# capmodule.net
KiCad netlist of a schematic drawn in EAGLE
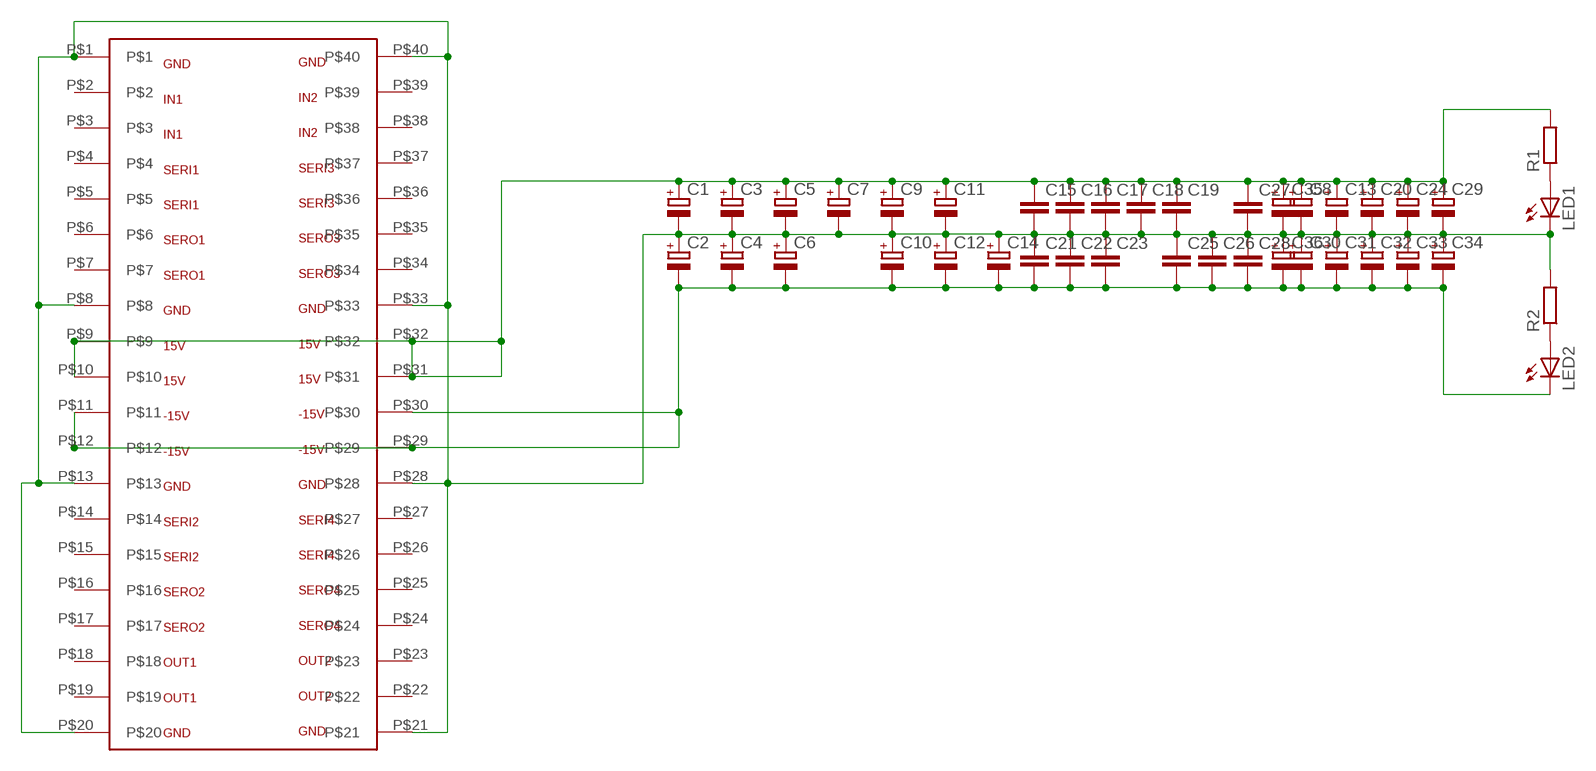
[diagram p0: schematic, sheet 1]

(export (version "E")
  (design (tool "Eeschema 10.0.6"))
  (components
    (comp (ref "C1")
      (value "CPOL-EUE3.5-8")
      (footprint "eagle-import:E3,5-8")
      (libsource (lib "eagle-import") (part "CPOL-EUE3.5-8"))
    )
    (comp (ref "C2")
      (value "CPOL-EUE3.5-8")
      (footprint "eagle-import:E3,5-8")
      (libsource (lib "eagle-import") (part "CPOL-EUE3.5-8"))
    )
    (comp (ref "C3")
      (value "CPOL-EUE3.5-8")
      (footprint "eagle-import:E3,5-8")
      (libsource (lib "eagle-import") (part "CPOL-EUE3.5-8"))
    )
    (comp (ref "C4")
      (value "CPOL-EUE3.5-8")
      (footprint "eagle-import:E3,5-8")
      (libsource (lib "eagle-import") (part "CPOL-EUE3.5-8"))
    )
    (comp (ref "C5")
      (value "CPOL-EUE3.5-8")
      (footprint "eagle-import:E3,5-8")
      (libsource (lib "eagle-import") (part "CPOL-EUE3.5-8"))
    )
    (comp (ref "C6")
      (value "CPOL-EUE3.5-8")
      (footprint "eagle-import:E3,5-8")
      (libsource (lib "eagle-import") (part "CPOL-EUE3.5-8"))
    )
    (comp (ref "C7")
      (value "CPOL-EUE3.5-8")
      (footprint "eagle-import:E3,5-8")
      (libsource (lib "eagle-import") (part "CPOL-EUE3.5-8"))
    )
    (comp (ref "C8")
      (value "CPOL-EUSP-CAP-CX")
      (footprint "eagle-import:SP-CAP-CX")
      (libsource (lib "eagle-import") (part "CPOL-EUSP-CAP-CX"))
    )
    (comp (ref "C9")
      (value "CPOL-EUE3.5-8")
      (footprint "eagle-import:E3,5-8")
      (libsource (lib "eagle-import") (part "CPOL-EUE3.5-8"))
    )
    (comp (ref "C10")
      (value "CPOL-EUE3.5-8")
      (footprint "eagle-import:E3,5-8")
      (libsource (lib "eagle-import") (part "CPOL-EUE3.5-8"))
    )
    (comp (ref "C11")
      (value "CPOL-EUE3.5-8")
      (footprint "eagle-import:E3,5-8")
      (libsource (lib "eagle-import") (part "CPOL-EUE3.5-8"))
    )
    (comp (ref "C12")
      (value "CPOL-EUE3.5-8")
      (footprint "eagle-import:E3,5-8")
      (libsource (lib "eagle-import") (part "CPOL-EUE3.5-8"))
    )
    (comp (ref "C13")
      (value "CPOL-EUSP-CAP-CX")
      (footprint "eagle-import:SP-CAP-CX")
      (libsource (lib "eagle-import") (part "CPOL-EUSP-CAP-CX"))
    )
    (comp (ref "C14")
      (value "CPOL-EUE3.5-8")
      (footprint "eagle-import:E3,5-8")
      (libsource (lib "eagle-import") (part "CPOL-EUE3.5-8"))
    )
    (comp (ref "C15")
      (value "C-EU050-035X075")
      (footprint "eagle-import:C050-035X075")
      (libsource (lib "eagle-import") (part "C-EU050-035X075"))
    )
    (comp (ref "C16")
      (value "C-EU050-035X075")
      (footprint "eagle-import:C050-035X075")
      (libsource (lib "eagle-import") (part "C-EU050-035X075"))
    )
    (comp (ref "C17")
      (value "C-EU050-035X075")
      (footprint "eagle-import:C050-035X075")
      (libsource (lib "eagle-import") (part "C-EU050-035X075"))
    )
    (comp (ref "C18")
      (value "C-EU050-035X075")
      (footprint "eagle-import:C050-035X075")
      (libsource (lib "eagle-import") (part "C-EU050-035X075"))
    )
    (comp (ref "C19")
      (value "C-EU050-035X075")
      (footprint "eagle-import:C050-035X075")
      (libsource (lib "eagle-import") (part "C-EU050-035X075"))
    )
    (comp (ref "C20")
      (value "CPOL-EUSP-CAP-CX")
      (footprint "eagle-import:SP-CAP-CX")
      (libsource (lib "eagle-import") (part "CPOL-EUSP-CAP-CX"))
    )
    (comp (ref "C21")
      (value "C-EU050-035X075")
      (footprint "eagle-import:C050-035X075")
      (libsource (lib "eagle-import") (part "C-EU050-035X075"))
    )
    (comp (ref "C22")
      (value "C-EU050-035X075")
      (footprint "eagle-import:C050-035X075")
      (libsource (lib "eagle-import") (part "C-EU050-035X075"))
    )
    (comp (ref "C23")
      (value "C-EU050-035X075")
      (footprint "eagle-import:C050-035X075")
      (libsource (lib "eagle-import") (part "C-EU050-035X075"))
    )
    (comp (ref "C24")
      (value "CPOL-EUSP-CAP-CX")
      (footprint "eagle-import:SP-CAP-CX")
      (libsource (lib "eagle-import") (part "CPOL-EUSP-CAP-CX"))
    )
    (comp (ref "C25")
      (value "C-EU050-035X075")
      (footprint "eagle-import:C050-035X075")
      (libsource (lib "eagle-import") (part "C-EU050-035X075"))
    )
    (comp (ref "C26")
      (value "C-EU050-035X075")
      (footprint "eagle-import:C050-035X075")
      (libsource (lib "eagle-import") (part "C-EU050-035X075"))
    )
    (comp (ref "C27")
      (value "C-EU050-035X075")
      (footprint "eagle-import:C050-035X075")
      (libsource (lib "eagle-import") (part "C-EU050-035X075"))
    )
    (comp (ref "C28")
      (value "C-EU050-035X075")
      (footprint "eagle-import:C050-035X075")
      (libsource (lib "eagle-import") (part "C-EU050-035X075"))
    )
    (comp (ref "C29")
      (value "CPOL-EUSP-CAP-CX")
      (footprint "eagle-import:SP-CAP-CX")
      (libsource (lib "eagle-import") (part "CPOL-EUSP-CAP-CX"))
    )
    (comp (ref "C30")
      (value "CPOL-EUSP-CAP-CX")
      (footprint "eagle-import:SP-CAP-CX")
      (libsource (lib "eagle-import") (part "CPOL-EUSP-CAP-CX"))
    )
    (comp (ref "C31")
      (value "CPOL-EUSP-CAP-CX")
      (footprint "eagle-import:SP-CAP-CX")
      (libsource (lib "eagle-import") (part "CPOL-EUSP-CAP-CX"))
    )
    (comp (ref "C32")
      (value "CPOL-EUSP-CAP-CX")
      (footprint "eagle-import:SP-CAP-CX")
      (libsource (lib "eagle-import") (part "CPOL-EUSP-CAP-CX"))
    )
    (comp (ref "C33")
      (value "CPOL-EUSP-CAP-CX")
      (footprint "eagle-import:SP-CAP-CX")
      (libsource (lib "eagle-import") (part "CPOL-EUSP-CAP-CX"))
    )
    (comp (ref "C34")
      (value "CPOL-EUSP-CAP-CX")
      (footprint "eagle-import:SP-CAP-CX")
      (libsource (lib "eagle-import") (part "CPOL-EUSP-CAP-CX"))
    )
    (comp (ref "C35")
      (value "CPOL-EUSP-CAP-CX")
      (footprint "eagle-import:SP-CAP-CX")
      (libsource (lib "eagle-import") (part "CPOL-EUSP-CAP-CX"))
    )
    (comp (ref "C36")
      (value "CPOL-EUSP-CAP-CX")
      (footprint "eagle-import:SP-CAP-CX")
      (libsource (lib "eagle-import") (part "CPOL-EUSP-CAP-CX"))
    )
    (comp (ref "LED1")
      (value "LEDSML1206")
      (footprint "eagle-import:SML1206")
      (libsource (lib "eagle-import") (part "LEDSML1206"))
    )
    (comp (ref "LED2")
      (value "LEDSML1206")
      (footprint "eagle-import:SML1206")
      (libsource (lib "eagle-import") (part "LEDSML1206"))
    )
    (comp (ref "R1")
      (value "R-EU_MELF0204W")
      (footprint "eagle-import:MINI_MELF-0204W")
      (libsource (lib "eagle-import") (part "R-EU_MELF0204W"))
    )
    (comp (ref "R2")
      (value "R-EU_MELF0204W")
      (footprint "eagle-import:MINI_MELF-0204W")
      (libsource (lib "eagle-import") (part "R-EU_MELF0204W"))
    )
    (comp (ref "U$1")
      (value "VDACA")
      (footprint "eagle-import:VDACA")
      (libsource (lib "eagle-import") (part "VDACA"))
    )
  )
  (nets
    (net (code "1") (name "Net-(C1-Pad+)") (class "Default")
      (node (ref "C1") (pin "+") (pinfunction "+_+") (pintype "passive"))
      (node (ref "C11") (pin "+") (pinfunction "+_+") (pintype "passive"))
      (node (ref "C13") (pin "+") (pinfunction "+_+") (pintype "passive"))
      (node (ref "C15") (pin "1") (pinfunction "1_1") (pintype "passive"))
      (node (ref "C16") (pin "1") (pinfunction "1_1") (pintype "passive"))
      (node (ref "C17") (pin "1") (pinfunction "1_1") (pintype "passive"))
      (node (ref "C18") (pin "1") (pinfunction "1_1") (pintype "passive"))
      (node (ref "C19") (pin "1") (pinfunction "1_1") (pintype "passive"))
      (node (ref "C20") (pin "+") (pinfunction "+_+") (pintype "passive"))
      (node (ref "C24") (pin "+") (pinfunction "+_+") (pintype "passive"))
      (node (ref "C27") (pin "1") (pinfunction "1_1") (pintype "passive"))
      (node (ref "C29") (pin "+") (pinfunction "+_+") (pintype "passive"))
      (node (ref "C3") (pin "+") (pinfunction "+_+") (pintype "passive"))
      (node (ref "C35") (pin "+") (pinfunction "+_+") (pintype "passive"))
      (node (ref "C5") (pin "+") (pinfunction "+_+") (pintype "passive"))
      (node (ref "C7") (pin "+") (pinfunction "+_+") (pintype "passive"))
      (node (ref "C8") (pin "+") (pinfunction "+_+") (pintype "passive"))
      (node (ref "C9") (pin "+") (pinfunction "+_+") (pintype "passive"))
      (node (ref "R1") (pin "2") (pinfunction "2_2") (pintype "passive"))
      (node (ref "U$1") (pin "P$10") (pinfunction "P$10_P$10") (pintype "bidirectional"))
      (node (ref "U$1") (pin "P$31") (pinfunction "P$31_P$31") (pintype "bidirectional"))
      (node (ref "U$1") (pin "P$32") (pinfunction "P$32_P$32") (pintype "bidirectional"))
      (node (ref "U$1") (pin "P$9") (pinfunction "P$9_P$9") (pintype "bidirectional"))
    )
    (net (code "2") (name "Net-(C1-Pad-)") (class "Default")
      (node (ref "C1") (pin "-") (pinfunction "-_-") (pintype "passive"))
      (node (ref "C10") (pin "+") (pinfunction "+_+") (pintype "passive"))
      (node (ref "C11") (pin "-") (pinfunction "-_-") (pintype "passive"))
      (node (ref "C12") (pin "+") (pinfunction "+_+") (pintype "passive"))
      (node (ref "C13") (pin "-") (pinfunction "-_-") (pintype "passive"))
      (node (ref "C14") (pin "+") (pinfunction "+_+") (pintype "passive"))
      (node (ref "C15") (pin "2") (pinfunction "2_2") (pintype "passive"))
      (node (ref "C16") (pin "2") (pinfunction "2_2") (pintype "passive"))
      (node (ref "C17") (pin "2") (pinfunction "2_2") (pintype "passive"))
      (node (ref "C18") (pin "2") (pinfunction "2_2") (pintype "passive"))
      (node (ref "C19") (pin "2") (pinfunction "2_2") (pintype "passive"))
      (node (ref "C2") (pin "+") (pinfunction "+_+") (pintype "passive"))
      (node (ref "C20") (pin "-") (pinfunction "-_-") (pintype "passive"))
      (node (ref "C21") (pin "1") (pinfunction "1_1") (pintype "passive"))
      (node (ref "C22") (pin "1") (pinfunction "1_1") (pintype "passive"))
      (node (ref "C23") (pin "1") (pinfunction "1_1") (pintype "passive"))
      (node (ref "C24") (pin "-") (pinfunction "-_-") (pintype "passive"))
      (node (ref "C25") (pin "1") (pinfunction "1_1") (pintype "passive"))
      (node (ref "C26") (pin "1") (pinfunction "1_1") (pintype "passive"))
      (node (ref "C27") (pin "2") (pinfunction "2_2") (pintype "passive"))
      (node (ref "C28") (pin "1") (pinfunction "1_1") (pintype "passive"))
      (node (ref "C29") (pin "-") (pinfunction "-_-") (pintype "passive"))
      (node (ref "C3") (pin "-") (pinfunction "-_-") (pintype "passive"))
      (node (ref "C30") (pin "+") (pinfunction "+_+") (pintype "passive"))
      (node (ref "C31") (pin "+") (pinfunction "+_+") (pintype "passive"))
      (node (ref "C32") (pin "+") (pinfunction "+_+") (pintype "passive"))
      (node (ref "C33") (pin "+") (pinfunction "+_+") (pintype "passive"))
      (node (ref "C34") (pin "+") (pinfunction "+_+") (pintype "passive"))
      (node (ref "C35") (pin "-") (pinfunction "-_-") (pintype "passive"))
      (node (ref "C36") (pin "+") (pinfunction "+_+") (pintype "passive"))
      (node (ref "C4") (pin "+") (pinfunction "+_+") (pintype "passive"))
      (node (ref "C5") (pin "-") (pinfunction "-_-") (pintype "passive"))
      (node (ref "C6") (pin "+") (pinfunction "+_+") (pintype "passive"))
      (node (ref "C7") (pin "-") (pinfunction "-_-") (pintype "passive"))
      (node (ref "C8") (pin "-") (pinfunction "-_-") (pintype "passive"))
      (node (ref "C9") (pin "-") (pinfunction "-_-") (pintype "passive"))
      (node (ref "LED1") (pin "C") (pinfunction "C_C") (pintype "passive"))
      (node (ref "R2") (pin "2") (pinfunction "2_2") (pintype "passive"))
      (node (ref "U$1") (pin "P$1") (pinfunction "P$1_P$1") (pintype "bidirectional"))
      (node (ref "U$1") (pin "P$13") (pinfunction "P$13_P$13") (pintype "bidirectional"))
      (node (ref "U$1") (pin "P$20") (pinfunction "P$20_P$20") (pintype "bidirectional"))
      (node (ref "U$1") (pin "P$21") (pinfunction "P$21_P$21") (pintype "bidirectional"))
      (node (ref "U$1") (pin "P$28") (pinfunction "P$28_P$28") (pintype "bidirectional"))
      (node (ref "U$1") (pin "P$33") (pinfunction "P$33_P$33") (pintype "bidirectional"))
      (node (ref "U$1") (pin "P$40") (pinfunction "P$40_P$40") (pintype "bidirectional"))
      (node (ref "U$1") (pin "P$8") (pinfunction "P$8_P$8") (pintype "bidirectional"))
    )
    (net (code "3") (name "Net-(C10-Pad-)") (class "Default")
      (node (ref "C10") (pin "-") (pinfunction "-_-") (pintype "passive"))
      (node (ref "C12") (pin "-") (pinfunction "-_-") (pintype "passive"))
      (node (ref "C14") (pin "-") (pinfunction "-_-") (pintype "passive"))
      (node (ref "C2") (pin "-") (pinfunction "-_-") (pintype "passive"))
      (node (ref "C21") (pin "2") (pinfunction "2_2") (pintype "passive"))
      (node (ref "C22") (pin "2") (pinfunction "2_2") (pintype "passive"))
      (node (ref "C23") (pin "2") (pinfunction "2_2") (pintype "passive"))
      (node (ref "C25") (pin "2") (pinfunction "2_2") (pintype "passive"))
      (node (ref "C26") (pin "2") (pinfunction "2_2") (pintype "passive"))
      (node (ref "C28") (pin "2") (pinfunction "2_2") (pintype "passive"))
      (node (ref "C30") (pin "-") (pinfunction "-_-") (pintype "passive"))
      (node (ref "C31") (pin "-") (pinfunction "-_-") (pintype "passive"))
      (node (ref "C32") (pin "-") (pinfunction "-_-") (pintype "passive"))
      (node (ref "C33") (pin "-") (pinfunction "-_-") (pintype "passive"))
      (node (ref "C34") (pin "-") (pinfunction "-_-") (pintype "passive"))
      (node (ref "C36") (pin "-") (pinfunction "-_-") (pintype "passive"))
      (node (ref "C4") (pin "-") (pinfunction "-_-") (pintype "passive"))
      (node (ref "C6") (pin "-") (pinfunction "-_-") (pintype "passive"))
      (node (ref "LED2") (pin "C") (pinfunction "C_C") (pintype "passive"))
      (node (ref "U$1") (pin "P$11") (pinfunction "P$11_P$11") (pintype "bidirectional"))
      (node (ref "U$1") (pin "P$12") (pinfunction "P$12_P$12") (pintype "bidirectional"))
      (node (ref "U$1") (pin "P$29") (pinfunction "P$29_P$29") (pintype "bidirectional"))
      (node (ref "U$1") (pin "P$30") (pinfunction "P$30_P$30") (pintype "bidirectional"))
    )
    (net (code "4") (name "Net-(LED1-PadA)") (class "Default")
      (node (ref "LED1") (pin "A") (pinfunction "A_A") (pintype "passive"))
      (node (ref "R1") (pin "1") (pinfunction "1_1") (pintype "passive"))
    )
    (net (code "5") (name "Net-(LED2-PadA)") (class "Default")
      (node (ref "LED2") (pin "A") (pinfunction "A_A") (pintype "passive"))
      (node (ref "R2") (pin "1") (pinfunction "1_1") (pintype "passive"))
    )
    (net (code "6") (name "unconnected-(U$1-PadP$2)") (class "Default")
      (node (ref "U$1") (pin "P$2") (pinfunction "P$2_P$2") (pintype "bidirectional"))
    )
    (net (code "7") (name "unconnected-(U$1-PadP$3)") (class "Default")
      (node (ref "U$1") (pin "P$3") (pinfunction "P$3_P$3") (pintype "bidirectional"))
    )
    (net (code "8") (name "unconnected-(U$1-PadP$4)") (class "Default")
      (node (ref "U$1") (pin "P$4") (pinfunction "P$4_P$4") (pintype "bidirectional"))
    )
    (net (code "9") (name "unconnected-(U$1-PadP$5)") (class "Default")
      (node (ref "U$1") (pin "P$5") (pinfunction "P$5_P$5") (pintype "bidirectional"))
    )
    (net (code "10") (name "unconnected-(U$1-PadP$6)") (class "Default")
      (node (ref "U$1") (pin "P$6") (pinfunction "P$6_P$6") (pintype "bidirectional"))
    )
    (net (code "11") (name "unconnected-(U$1-PadP$7)") (class "Default")
      (node (ref "U$1") (pin "P$7") (pinfunction "P$7_P$7") (pintype "bidirectional"))
    )
    (net (code "12") (name "unconnected-(U$1-PadP$14)") (class "Default")
      (node (ref "U$1") (pin "P$14") (pinfunction "P$14_P$14") (pintype "bidirectional"))
    )
    (net (code "13") (name "unconnected-(U$1-PadP$15)") (class "Default")
      (node (ref "U$1") (pin "P$15") (pinfunction "P$15_P$15") (pintype "bidirectional"))
    )
    (net (code "14") (name "unconnected-(U$1-PadP$16)") (class "Default")
      (node (ref "U$1") (pin "P$16") (pinfunction "P$16_P$16") (pintype "bidirectional"))
    )
    (net (code "15") (name "unconnected-(U$1-PadP$17)") (class "Default")
      (node (ref "U$1") (pin "P$17") (pinfunction "P$17_P$17") (pintype "bidirectional"))
    )
    (net (code "16") (name "unconnected-(U$1-PadP$18)") (class "Default")
      (node (ref "U$1") (pin "P$18") (pinfunction "P$18_P$18") (pintype "bidirectional"))
    )
    (net (code "17") (name "unconnected-(U$1-PadP$19)") (class "Default")
      (node (ref "U$1") (pin "P$19") (pinfunction "P$19_P$19") (pintype "bidirectional"))
    )
    (net (code "18") (name "unconnected-(U$1-PadP$22)") (class "Default")
      (node (ref "U$1") (pin "P$22") (pinfunction "P$22_P$22") (pintype "bidirectional"))
    )
    (net (code "19") (name "unconnected-(U$1-PadP$23)") (class "Default")
      (node (ref "U$1") (pin "P$23") (pinfunction "P$23_P$23") (pintype "bidirectional"))
    )
    (net (code "20") (name "unconnected-(U$1-PadP$24)") (class "Default")
      (node (ref "U$1") (pin "P$24") (pinfunction "P$24_P$24") (pintype "bidirectional"))
    )
    (net (code "21") (name "unconnected-(U$1-PadP$25)") (class "Default")
      (node (ref "U$1") (pin "P$25") (pinfunction "P$25_P$25") (pintype "bidirectional"))
    )
    (net (code "22") (name "unconnected-(U$1-PadP$26)") (class "Default")
      (node (ref "U$1") (pin "P$26") (pinfunction "P$26_P$26") (pintype "bidirectional"))
    )
    (net (code "23") (name "unconnected-(U$1-PadP$27)") (class "Default")
      (node (ref "U$1") (pin "P$27") (pinfunction "P$27_P$27") (pintype "bidirectional"))
    )
    (net (code "24") (name "unconnected-(U$1-PadP$34)") (class "Default")
      (node (ref "U$1") (pin "P$34") (pinfunction "P$34_P$34") (pintype "bidirectional"))
    )
    (net (code "25") (name "unconnected-(U$1-PadP$35)") (class "Default")
      (node (ref "U$1") (pin "P$35") (pinfunction "P$35_P$35") (pintype "bidirectional"))
    )
    (net (code "26") (name "unconnected-(U$1-PadP$36)") (class "Default")
      (node (ref "U$1") (pin "P$36") (pinfunction "P$36_P$36") (pintype "bidirectional"))
    )
    (net (code "27") (name "unconnected-(U$1-PadP$37)") (class "Default")
      (node (ref "U$1") (pin "P$37") (pinfunction "P$37_P$37") (pintype "bidirectional"))
    )
    (net (code "28") (name "unconnected-(U$1-PadP$38)") (class "Default")
      (node (ref "U$1") (pin "P$38") (pinfunction "P$38_P$38") (pintype "bidirectional"))
    )
    (net (code "29") (name "unconnected-(U$1-PadP$39)") (class "Default")
      (node (ref "U$1") (pin "P$39") (pinfunction "P$39_P$39") (pintype "bidirectional"))
    )
  )
)
